# Contactor.net
KiCad netlist of a schematic drawn in Altium Designer
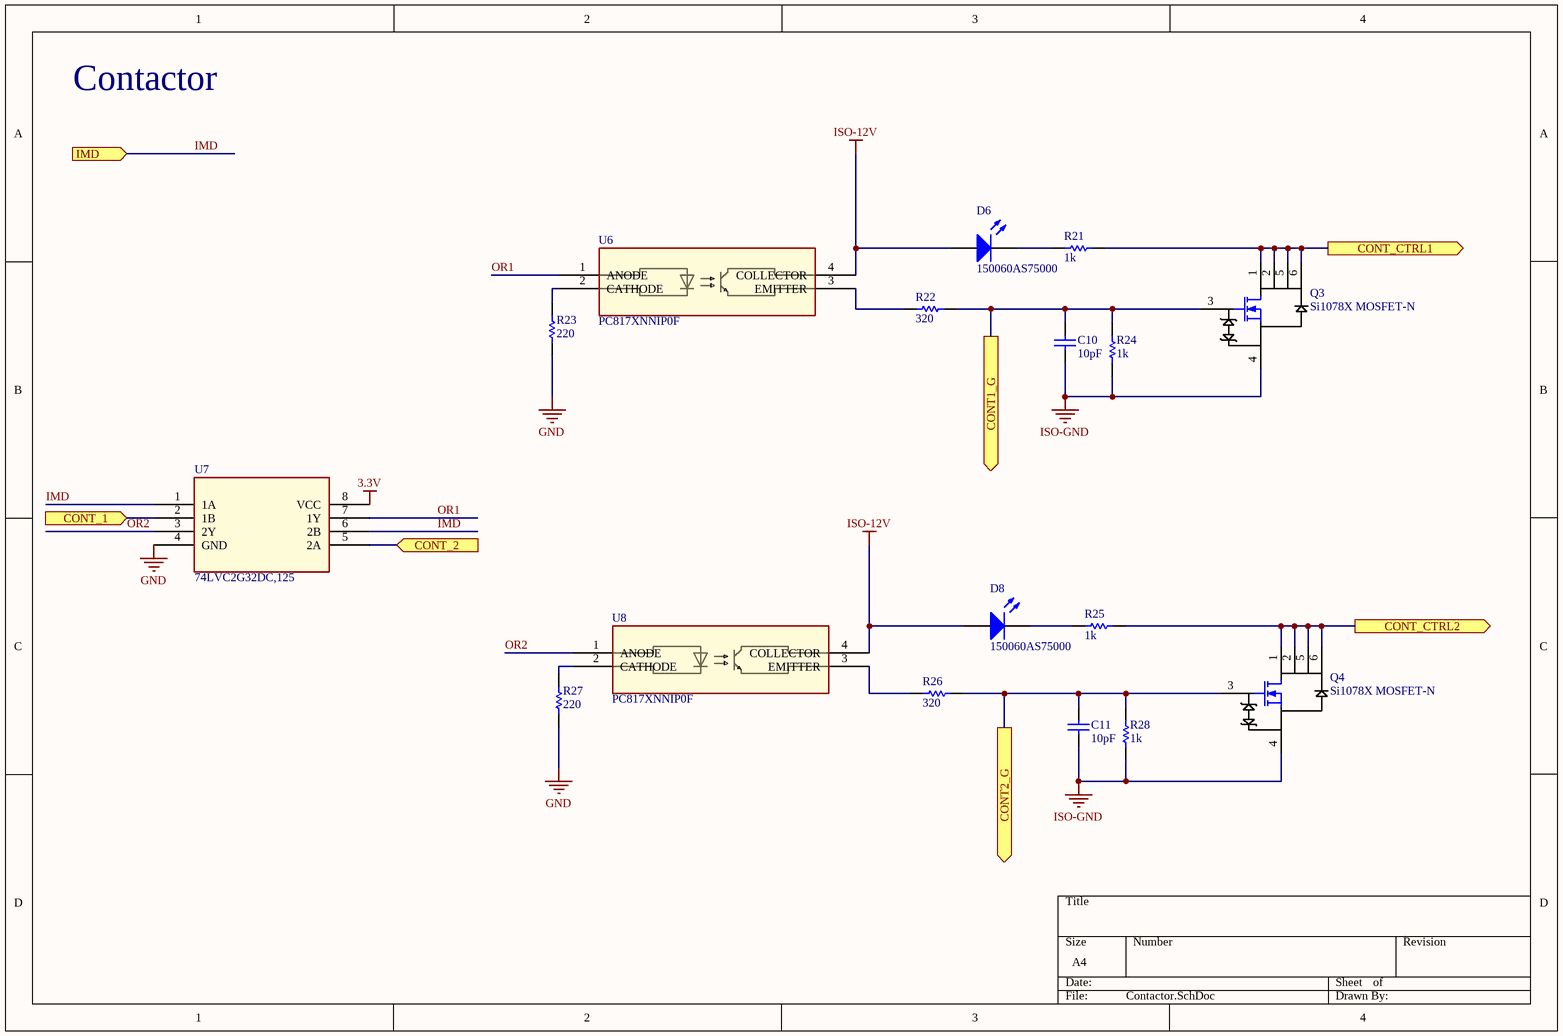
[diagram p0: Contactor.SchDoc]

(export (version "E")
  (design (tool "Eeschema 10.0.6"))
  (components
    (comp (ref "C10")
      (value "10pF")
      (footprint "0603 - Capacitor")
      (description "Nonpolarized Capacitor")
      (fields (field (name "Comment") "Capacitor - Nonpolarized"))
      (libsource (lib "General") (part "Capacitor - Nonpolarized"))
    )
    (comp (ref "C11")
      (value "10pF")
      (footprint "0603 - Capacitor")
      (description "Nonpolarized Capacitor")
      (fields (field (name "Comment") "Capacitor - Nonpolarized"))
      (libsource (lib "General") (part "Capacitor - Nonpolarized"))
    )
    (comp (ref "D6")
      (value "150060AS75000")
      (footprint "0603 - Resistor")
      (description "Amber 605nm LED Indication - Discrete 2V 0603 (1608 Metric)")
      (fields (field (name "MANUFACTURER") "Würth Elektronik"))
      (libsource (lib "General") (part "LED"))
    )
    (comp (ref "D8")
      (value "150060AS75000")
      (footprint "0603 - Resistor")
      (description "Amber 605nm LED Indication - Discrete 2V 0603 (1608 Metric)")
      (fields (field (name "MANUFACTURER") "Würth Elektronik"))
      (libsource (lib "General") (part "LED"))
    )
    (comp (ref "Q3")
      (value "Si1078X MOSFET-N")
      (footprint "Si1078X NMOS 30V")
      (description "N-Channel 30 V (D-S) MOSFET")
      (fields (field (name "MANUFACTURER PART NUMBER") "SI1078X-T1-GE3"))
      (libsource (lib "General") (part "Si1078X MOSFET-N"))
    )
    (comp (ref "Q4")
      (value "Si1078X MOSFET-N")
      (footprint "Si1078X NMOS 30V")
      (description "N-Channel 30 V (D-S) MOSFET")
      (fields (field (name "MANUFACTURER PART NUMBER") "SI1078X-T1-GE3"))
      (libsource (lib "General") (part "Si1078X MOSFET-N"))
    )
    (comp (ref "R21")
      (value "1k")
      (footprint "0603 - Resistor")
      (description "Resistor")
      (libsource (lib "General") (part "Resistor"))
    )
    (comp (ref "R22")
      (value "320")
      (footprint "0603 - Resistor")
      (description "Resistor")
      (libsource (lib "General") (part "Resistor"))
    )
    (comp (ref "R23")
      (value "220")
      (footprint "0603 - Resistor")
      (description "Resistor")
      (libsource (lib "General") (part "Resistor"))
    )
    (comp (ref "R24")
      (value "1k")
      (footprint "0603 - Resistor")
      (description "Resistor")
      (libsource (lib "General") (part "Resistor"))
    )
    (comp (ref "R25")
      (value "1k")
      (footprint "0603 - Resistor")
      (description "Resistor")
      (libsource (lib "General") (part "Resistor"))
    )
    (comp (ref "R26")
      (value "320")
      (footprint "0603 - Resistor")
      (description "Resistor")
      (libsource (lib "General") (part "Resistor"))
    )
    (comp (ref "R27")
      (value "220")
      (footprint "0603 - Resistor")
      (description "Resistor")
      (libsource (lib "General") (part "Resistor"))
    )
    (comp (ref "R28")
      (value "1k")
      (footprint "0603 - Resistor")
      (description "Resistor")
      (libsource (lib "General") (part "Resistor"))
    )
    (comp (ref "U6")
      (value "PC817XNNIP0F")
      (footprint "PC817XNNIP0F_SHP")
      (description "Transistor Output Optocouplers Photocoupler")
      (libsource (lib "BMS") (part "PC817XNNIP0F"))
    )
    (comp (ref "U7")
      (value "74LVC2G32DC,125")
      (footprint "VSSOP8_SOT765-1_NEX")
      (description "IC GATE OR 2CH 2-INP 8TSSOP")
      (libsource (lib "General") (part "74LVC2G32DC,125"))
    )
    (comp (ref "U8")
      (value "PC817XNNIP0F")
      (footprint "PC817XNNIP0F_SHP")
      (description "Transistor Output Optocouplers Photocoupler")
      (libsource (lib "BMS") (part "PC817XNNIP0F"))
    )
  )
  (nets
    (net (code "1") (name "/CONT1_G") (class "Default")
      (node (ref "C10") (pin "2") (pinfunction "2_2") (pintype "passive"))
      (node (ref "Q3") (pin "3") (pinfunction "3_3") (pintype "passive"))
      (node (ref "R22") (pin "2") (pinfunction "2_2") (pintype "passive"))
      (node (ref "R24") (pin "2") (pinfunction "2_2") (pintype "passive"))
    )
    (net (code "2") (name "/CONT2_G") (class "Default")
      (node (ref "C11") (pin "2") (pinfunction "2_2") (pintype "passive"))
      (node (ref "Q4") (pin "3") (pinfunction "3_3") (pintype "passive"))
      (node (ref "R26") (pin "2") (pinfunction "2_2") (pintype "passive"))
      (node (ref "R28") (pin "2") (pinfunction "2_2") (pintype "passive"))
    )
    (net (code "3") (name "/CONT_1") (class "Default")
      (node (ref "U7") (pin "2") (pinfunction "1B_2") (pintype "passive"))
    )
    (net (code "4") (name "/CONT_2") (class "Default")
      (node (ref "U7") (pin "5") (pinfunction "2A_5") (pintype "passive"))
    )
    (net (code "5") (name "/CONT_CTRL1") (class "Default")
      (node (ref "Q3") (pin "1") (pinfunction "G_1") (pintype "passive"))
      (node (ref "Q3") (pin "2") (pinfunction "D_2") (pintype "passive"))
      (node (ref "Q3") (pin "5") (pinfunction "5_5") (pintype "passive"))
      (node (ref "Q3") (pin "6") (pinfunction "6_6") (pintype "passive"))
      (node (ref "R21") (pin "1") (pinfunction "1_1") (pintype "passive"))
    )
    (net (code "6") (name "/CONT_CTRL2") (class "Default")
      (node (ref "Q4") (pin "1") (pinfunction "G_1") (pintype "passive"))
      (node (ref "Q4") (pin "2") (pinfunction "D_2") (pintype "passive"))
      (node (ref "Q4") (pin "5") (pinfunction "5_5") (pintype "passive"))
      (node (ref "Q4") (pin "6") (pinfunction "6_6") (pintype "passive"))
      (node (ref "R25") (pin "1") (pinfunction "1_1") (pintype "passive"))
    )
    (net (code "7") (name "/IMD") (class "Default")
      (node (ref "U7") (pin "1") (pinfunction "1A_1") (pintype "passive"))
      (node (ref "U7") (pin "6") (pinfunction "2B_6") (pintype "passive"))
    )
    (net (code "8") (name "/OR1") (class "Default")
      (node (ref "U6") (pin "1") (pinfunction "ANODE_1") (pintype "passive"))
      (node (ref "U7") (pin "7") (pinfunction "1Y_7") (pintype "passive"))
    )
    (net (code "9") (name "/OR2") (class "Default")
      (node (ref "U7") (pin "3") (pinfunction "2Y_3") (pintype "passive"))
      (node (ref "U8") (pin "1") (pinfunction "ANODE_1") (pintype "passive"))
    )
    (net (code "10") (name "3.3V") (class "Default")
      (node (ref "U7") (pin "8") (pinfunction "VCC_8") (pintype "power_in"))
    )
    (net (code "11") (name "GND") (class "Default")
      (node (ref "R23") (pin "1") (pinfunction "1_1") (pintype "passive"))
      (node (ref "R27") (pin "1") (pinfunction "1_1") (pintype "passive"))
      (node (ref "U7") (pin "4") (pinfunction "GND_4") (pintype "passive"))
    )
    (net (code "12") (name "ISO-12V") (class "Default")
      (node (ref "D6") (pin "1") (pinfunction "A_1") (pintype "passive"))
      (node (ref "D8") (pin "1") (pinfunction "A_1") (pintype "passive"))
      (node (ref "U6") (pin "4") (pinfunction "COLLECTOR_4") (pintype "passive"))
      (node (ref "U8") (pin "4") (pinfunction "COLLECTOR_4") (pintype "passive"))
    )
    (net (code "13") (name "ISO-GND") (class "Default")
      (node (ref "C10") (pin "1") (pinfunction "1_1") (pintype "passive"))
      (node (ref "C11") (pin "1") (pinfunction "1_1") (pintype "passive"))
      (node (ref "Q3") (pin "4") (pinfunction "4_4") (pintype "passive"))
      (node (ref "Q4") (pin "4") (pinfunction "4_4") (pintype "passive"))
      (node (ref "R24") (pin "1") (pinfunction "1_1") (pintype "passive"))
      (node (ref "R28") (pin "1") (pinfunction "1_1") (pintype "passive"))
    )
    (net (code "14") (name "Net-(D6-K)") (class "Default")
      (node (ref "D6") (pin "2") (pinfunction "K_2") (pintype "passive"))
      (node (ref "R21") (pin "2") (pinfunction "2_2") (pintype "passive"))
    )
    (net (code "15") (name "Net-(D8-K)") (class "Default")
      (node (ref "D8") (pin "2") (pinfunction "K_2") (pintype "passive"))
      (node (ref "R25") (pin "2") (pinfunction "2_2") (pintype "passive"))
    )
    (net (code "16") (name "Net-(U6-CATHODE)") (class "Default")
      (node (ref "R23") (pin "2") (pinfunction "2_2") (pintype "passive"))
      (node (ref "U6") (pin "2") (pinfunction "CATHODE_2") (pintype "passive"))
    )
    (net (code "17") (name "Net-(U6-EMITTER)") (class "Default")
      (node (ref "R22") (pin "1") (pinfunction "1_1") (pintype "passive"))
      (node (ref "U6") (pin "3") (pinfunction "EMITTER_3") (pintype "passive"))
    )
    (net (code "18") (name "Net-(U8-CATHODE)") (class "Default")
      (node (ref "R27") (pin "2") (pinfunction "2_2") (pintype "passive"))
      (node (ref "U8") (pin "2") (pinfunction "CATHODE_2") (pintype "passive"))
    )
    (net (code "19") (name "Net-(U8-EMITTER)") (class "Default")
      (node (ref "R26") (pin "1") (pinfunction "1_1") (pintype "passive"))
      (node (ref "U8") (pin "3") (pinfunction "EMITTER_3") (pintype "passive"))
    )
  )
)
